# V1_8.net
KiCad netlist of a schematic drawn in Altium Designer
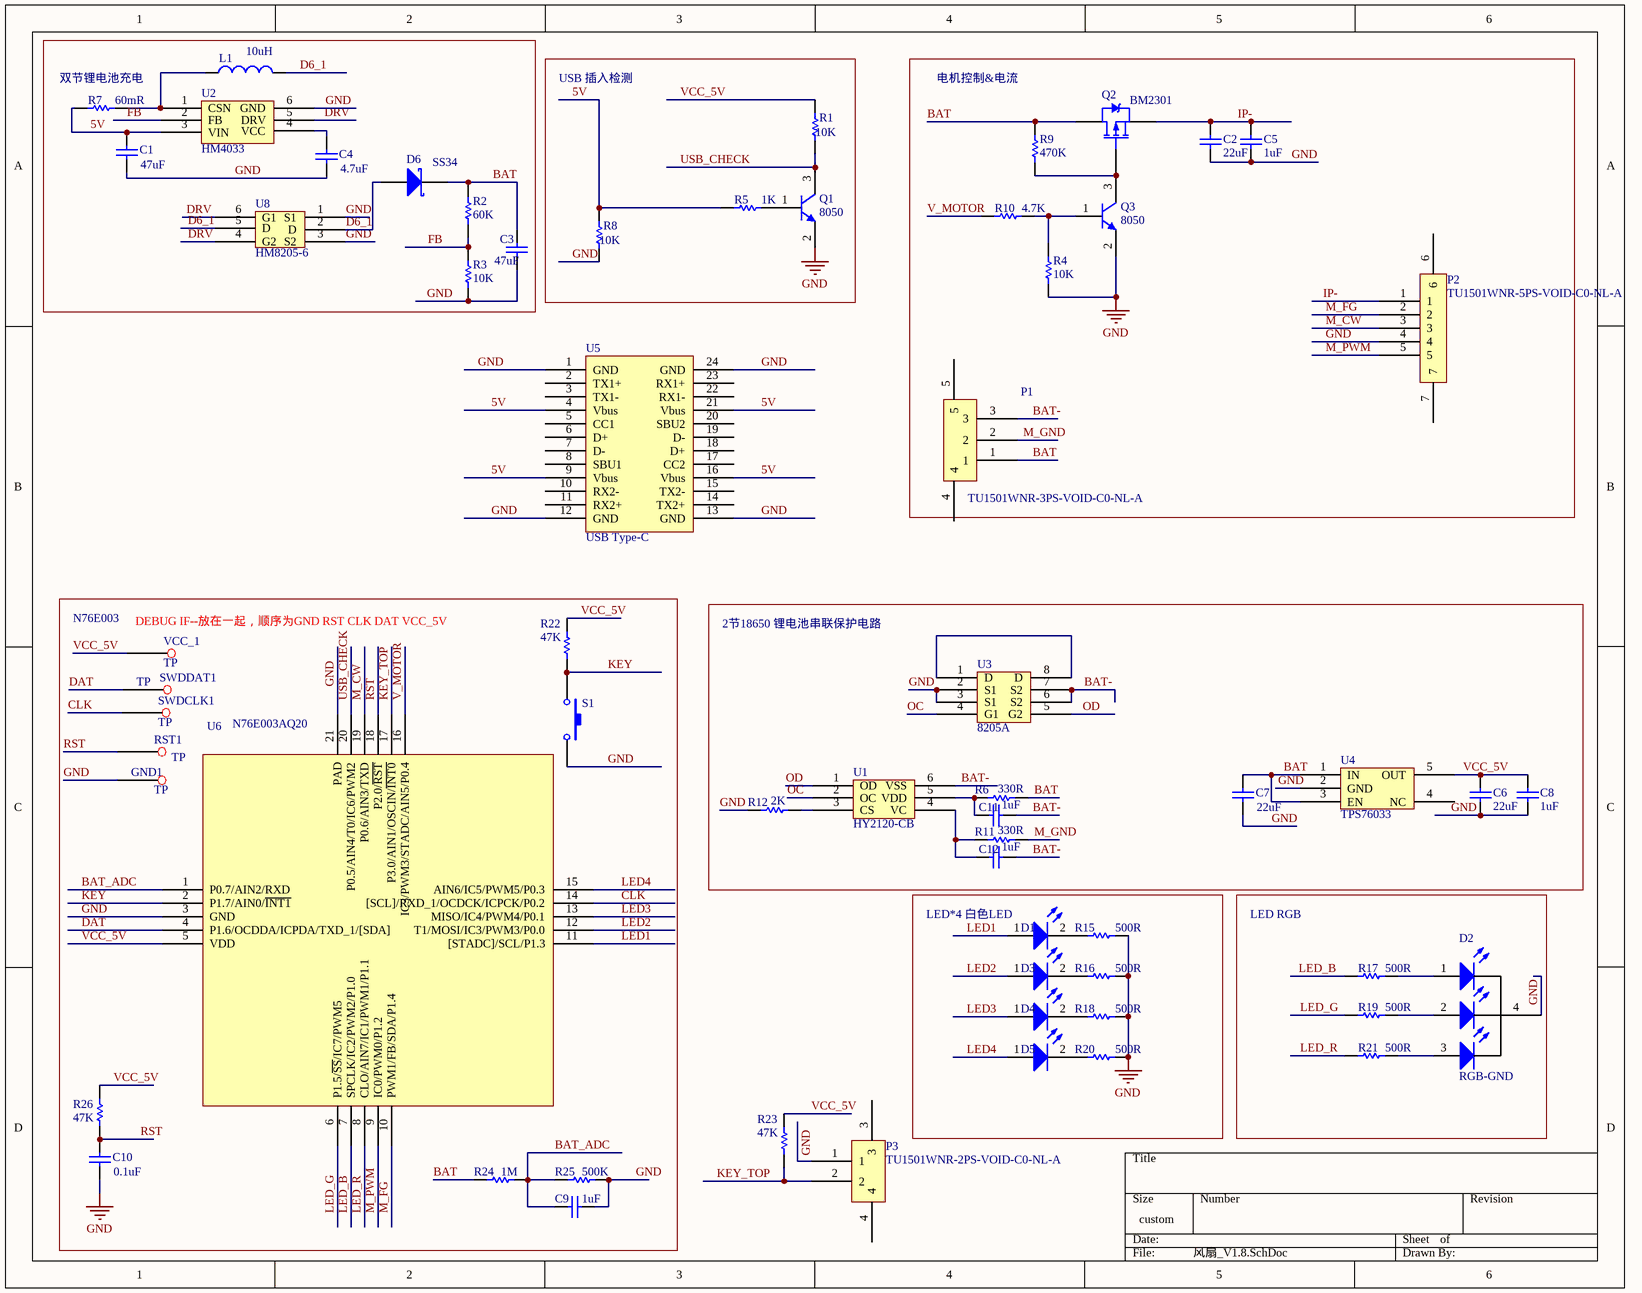
[diagram p0: 风扇_V1.8.SchDoc]

(export (version "E")
  (design (tool "Eeschema 10.0.6"))
  (components
    (comp (ref "C1")
      (value "47uF")
      (footprint "C-0603")
      (description "Capacitor")
      (fields (field (name "PUBLISHER") "Altium Limited"))
      (libsource (lib "Miscellaneous Devices") (part "Cap"))
    )
    (comp (ref "C2")
      (value "22uF")
      (footprint "C-0603")
      (description "Capacitor")
      (fields (field (name "PUBLISHER") "Altium Limited"))
      (libsource (lib "Miscellaneous Devices") (part "Cap"))
    )
    (comp (ref "C3")
      (value "47uF")
      (footprint "C-0603")
      (description "Capacitor")
      (fields (field (name "PUBLISHER") "Altium Limited"))
      (libsource (lib "Miscellaneous Devices") (part "Cap"))
    )
    (comp (ref "C4")
      (value "4.7uF")
      (footprint "C-0402")
      (description "Capacitor")
      (fields (field (name "PUBLISHER") "Altium Limited"))
      (libsource (lib "Miscellaneous Devices") (part "Cap"))
    )
    (comp (ref "C5")
      (value "1uF")
      (footprint "C-0402")
      (description "Capacitor")
      (fields (field (name "PUBLISHER") "Altium Limited"))
      (libsource (lib "Miscellaneous Devices") (part "Cap"))
    )
    (comp (ref "C6")
      (value "22uF")
      (footprint "C-0603")
      (description "Capacitor")
      (fields (field (name "PUBLISHER") "Altium Limited"))
      (libsource (lib "Miscellaneous Devices") (part "Cap"))
    )
    (comp (ref "C7")
      (value "22uF")
      (footprint "C-0603")
      (description "Capacitor")
      (fields (field (name "PUBLISHER") "Altium Limited"))
      (libsource (lib "Miscellaneous Devices") (part "Cap"))
    )
    (comp (ref "C8")
      (value "1uF")
      (footprint "C-0402")
      (description "Capacitor")
      (fields (field (name "PUBLISHER") "Altium Limited"))
      (libsource (lib "Miscellaneous Devices") (part "Cap"))
    )
    (comp (ref "C9")
      (value "1uF")
      (footprint "C-0402")
      (description "Capacitor")
      (fields (field (name "PUBLISHER") "Altium Limited"))
      (libsource (lib "Miscellaneous Devices") (part "Cap"))
    )
    (comp (ref "C10")
      (value "0.1uF")
      (footprint "C-0402")
      (description "Capacitor")
      (fields (field (name "PUBLISHER") "Altium Limited"))
      (libsource (lib "Miscellaneous Devices") (part "Cap"))
    )
    (comp (ref "C11")
      (value "1uF")
      (footprint "C-0402")
      (description "Capacitor")
      (fields (field (name "PUBLISHER") "Altium Limited"))
      (libsource (lib "Miscellaneous Devices") (part "Cap"))
    )
    (comp (ref "C12")
      (value "1uF")
      (footprint "C-0402")
      (description "Capacitor")
      (fields (field (name "PUBLISHER") "Altium Limited"))
      (libsource (lib "Miscellaneous Devices") (part "Cap"))
    )
    (comp (ref "D1")
      (value "LED0")
      (footprint "LED-0603")
      (description "Typical INFRARED GaAs LED")
      (fields (field (name "PUBLISHER") "Altium Limited"))
      (libsource (lib "Miscellaneous Devices") (part "LED0"))
    )
    (comp (ref "D2")
      (value "RGB-GND")
      (footprint "0603*2-LED")
      (libsource (lib "Others_IC_SCH_LIB") (part "RGB-GND"))
    )
    (comp (ref "D3")
      (value "LED0")
      (footprint "LED-0603")
      (description "Typical INFRARED GaAs LED")
      (fields (field (name "PUBLISHER") "Altium Limited"))
      (libsource (lib "Miscellaneous Devices") (part "LED0"))
    )
    (comp (ref "D4")
      (value "LED0")
      (footprint "LED-0603")
      (description "Typical INFRARED GaAs LED")
      (fields (field (name "PUBLISHER") "Altium Limited"))
      (libsource (lib "Miscellaneous Devices") (part "LED0"))
    )
    (comp (ref "D5")
      (value "LED0")
      (footprint "LED-0603")
      (description "Typical INFRARED GaAs LED")
      (fields (field (name "PUBLISHER") "Altium Limited"))
      (libsource (lib "Miscellaneous Devices") (part "LED0"))
    )
    (comp (ref "D6")
      (value "SS34")
      (footprint "HM4033 V1.0:DSMD")
      (description "Schottky Rectifier")
      (fields (field (name "PUBLISHER") "Altium Limited"))
      (libsource (lib "Miscellaneous Devices") (part "Diode 10TQ035"))
    )
    (comp (ref "GND1") (value "TP") (footprint "TP-1.5") (libsource (lib "Others_IC_SCH_LIB") (part "TP")))
    (comp (ref "L1")
      (value "10uH")
      (footprint "L-SMD")
      (description "Inductor")
      (fields (field (name "PUBLISHER") "Altium Limited"))
      (libsource (lib "Miscellaneous Devices") (part "Inductor"))
    )
    (comp (ref "P1")
      (value "TU1501WNR-3PS-VOID-C0-NL-A")
      (footprint "TU1501WNR-3PS-VOID-*-NL-A")
      (libsource (lib "Others_IC_SCH_LIB") (part "TU1501WNR-3PS-VOID-C0-NL-A"))
    )
    (comp (ref "P2")
      (value "TU1501WNR-5PS-VOID-C0-NL-A")
      (footprint "TU1501WNR-5PS-VOID-*-NL-A")
      (libsource (lib "Others_IC_SCH_LIB") (part "TU1501WNR-5PS-VOID-C0-NL-A"))
    )
    (comp (ref "P3")
      (value "TU1501WNR-2PS-VOID-C0-NL-A")
      (footprint "TU1501WNR-2PS-VOID-*-NL-A")
      (libsource (lib "Others_IC_SCH_LIB") (part "TU1501WNR-2PS-VOID-C0-NL-A"))
    )
    (comp (ref "Q1")
      (value "8050")
      (footprint "SOT-23")
      (description "NPN Bipolar Transistor")
      (fields (field (name "PUBLISHER") "Altium Limited"))
      (libsource (lib "Miscellaneous Devices") (part "NPN"))
    )
    (comp (ref "Q2")
      (value "BM2301")
      (footprint "SOT-23")
      (description "P-Channel Power MOSFET")
      (fields (field (name "PUBLISHER") "Altium Limited"))
      (libsource (lib "Miscellaneous Devices") (part "PMOS-2"))
    )
    (comp (ref "Q3")
      (value "8050")
      (footprint "SOT-23")
      (description "NPN Bipolar Transistor")
      (fields (field (name "PUBLISHER") "Altium Limited"))
      (libsource (lib "Miscellaneous Devices") (part "NPN"))
    )
    (comp (ref "R1")
      (value "10K")
      (footprint "R-0402")
      (description "Resistor")
      (fields (field (name "PUBLISHER") "Altium Limited"))
      (libsource (lib "Miscellaneous Devices") (part "Res1"))
    )
    (comp (ref "R2")
      (value "60K")
      (footprint "R-0402")
      (description "Resistor")
      (fields (field (name "PUBLISHER") "Altium Limited"))
      (libsource (lib "Miscellaneous Devices") (part "Res1"))
    )
    (comp (ref "R3")
      (value "10K")
      (footprint "R-0402")
      (description "Resistor")
      (fields (field (name "PUBLISHER") "Altium Limited"))
      (libsource (lib "Miscellaneous Devices") (part "Res1"))
    )
    (comp (ref "R4")
      (value "10K")
      (footprint "R-0402")
      (description "Resistor")
      (fields (field (name "PUBLISHER") "Altium Limited"))
      (libsource (lib "Miscellaneous Devices") (part "Res1"))
    )
    (comp (ref "R5")
      (value "1K")
      (footprint "R-0402")
      (description "Resistor")
      (fields (field (name "PUBLISHER") "Altium Limited"))
      (libsource (lib "Miscellaneous Devices") (part "Res1"))
    )
    (comp (ref "R6")
      (value "330R")
      (footprint "R-0402")
      (description "Resistor")
      (fields (field (name "PUBLISHER") "Altium Limited"))
      (libsource (lib "Miscellaneous Devices") (part "Res1"))
    )
    (comp (ref "R7")
      (value "60mR")
      (footprint "R-0402")
      (description "Resistor")
      (fields (field (name "PUBLISHER") "Altium Limited"))
      (libsource (lib "Miscellaneous Devices") (part "Res1"))
    )
    (comp (ref "R8")
      (value "10K")
      (footprint "R-0402")
      (description "Resistor")
      (fields (field (name "PUBLISHER") "Altium Limited"))
      (libsource (lib "Miscellaneous Devices") (part "Res1"))
    )
    (comp (ref "R9")
      (value "470K")
      (footprint "R-0402")
      (description "Resistor")
      (fields (field (name "PUBLISHER") "Altium Limited"))
      (libsource (lib "Miscellaneous Devices") (part "Res1"))
    )
    (comp (ref "R10")
      (value "4.7K")
      (footprint "R-0402")
      (description "Resistor")
      (fields (field (name "PUBLISHER") "Altium Limited"))
      (libsource (lib "Miscellaneous Devices") (part "Res1"))
    )
    (comp (ref "R11")
      (value "330R")
      (footprint "R-0402")
      (description "Resistor")
      (fields (field (name "PUBLISHER") "Altium Limited"))
      (libsource (lib "Miscellaneous Devices") (part "Res1"))
    )
    (comp (ref "R12")
      (value "2K")
      (footprint "R-0402")
      (description "Resistor")
      (fields (field (name "PUBLISHER") "Altium Limited"))
      (libsource (lib "Miscellaneous Devices") (part "Res1"))
    )
    (comp (ref "R15")
      (value "500R")
      (footprint "R-0402")
      (description "Resistor")
      (fields (field (name "PUBLISHER") "Altium Limited"))
      (libsource (lib "Miscellaneous Devices") (part "Res1"))
    )
    (comp (ref "R16")
      (value "500R")
      (footprint "R-0402")
      (description "Resistor")
      (fields (field (name "PUBLISHER") "Altium Limited"))
      (libsource (lib "Miscellaneous Devices") (part "Res1"))
    )
    (comp (ref "R17")
      (value "500R")
      (footprint "R-0402")
      (description "Resistor")
      (fields (field (name "PUBLISHER") "Altium Limited"))
      (libsource (lib "Miscellaneous Devices") (part "Res1"))
    )
    (comp (ref "R18")
      (value "500R")
      (footprint "R-0402")
      (description "Resistor")
      (fields (field (name "PUBLISHER") "Altium Limited"))
      (libsource (lib "Miscellaneous Devices") (part "Res1"))
    )
    (comp (ref "R19")
      (value "500R")
      (footprint "R-0402")
      (description "Resistor")
      (fields (field (name "PUBLISHER") "Altium Limited"))
      (libsource (lib "Miscellaneous Devices") (part "Res1"))
    )
    (comp (ref "R20")
      (value "500R")
      (footprint "R-0402")
      (description "Resistor")
      (fields (field (name "PUBLISHER") "Altium Limited"))
      (libsource (lib "Miscellaneous Devices") (part "Res1"))
    )
    (comp (ref "R21")
      (value "500R")
      (footprint "R-0402")
      (description "Resistor")
      (fields (field (name "PUBLISHER") "Altium Limited"))
      (libsource (lib "Miscellaneous Devices") (part "Res1"))
    )
    (comp (ref "R22")
      (value "47K")
      (footprint "R-0402")
      (description "Resistor")
      (fields (field (name "PUBLISHER") "Altium Limited"))
      (libsource (lib "Miscellaneous Devices") (part "Res1"))
    )
    (comp (ref "R23")
      (value "47K")
      (footprint "R-0402")
      (description "Resistor")
      (fields (field (name "PUBLISHER") "Altium Limited"))
      (libsource (lib "Miscellaneous Devices") (part "Res1"))
    )
    (comp (ref "R24")
      (value "1M")
      (footprint "R-0402")
      (description "Resistor")
      (fields (field (name "PUBLISHER") "Altium Limited"))
      (libsource (lib "Miscellaneous Devices") (part "Res1"))
    )
    (comp (ref "R25")
      (value "500K")
      (footprint "R-0402")
      (description "Resistor")
      (fields (field (name "PUBLISHER") "Altium Limited"))
      (libsource (lib "Miscellaneous Devices") (part "Res1"))
    )
    (comp (ref "R26")
      (value "47K")
      (footprint "R-0402")
      (description "Resistor")
      (fields (field (name "PUBLISHER") "Altium Limited"))
      (libsource (lib "Miscellaneous Devices") (part "Res1"))
    )
    (comp (ref "RST1") (value "TP") (footprint "TP-1.5") (libsource (lib "Others_IC_SCH_LIB") (part "TP")))
    (comp (ref "S1")
      (value "SW-PB")
      (footprint "SWITCH-4P-SMT")
      (description "Switch")
      (fields (field (name "PUBLISHER") "Altium Limited"))
      (libsource (lib "Miscellaneous Devices") (part "SW-PB"))
    )
    (comp (ref "SWDCLK1") (value "TP") (footprint "TP-1.5") (libsource (lib "Others_IC_SCH_LIB") (part "TP")))
    (comp (ref "SWDDAT1") (value "TP") (footprint "TP-1.5") (libsource (lib "Others_IC_SCH_LIB") (part "TP")))
    (comp (ref "U1")
      (value "HY2120-CB")
      (footprint "SOT-23-6L")
      (libsource (lib "Others_IC_SCH_LIB") (part "HY2120"))
    )
    (comp (ref "U2")
      (value "HM4033")
      (footprint "SOT-23-6L")
      (libsource (lib "Others_IC_SCH_LIB") (part "HM4033"))
    )
    (comp (ref "U3")
      (value "8205A")
      (footprint "TSSOP8")
      (libsource (lib "Others_IC_SCH_LIB") (part "8205A"))
    )
    (comp (ref "U4")
      (value "TPS76033")
      (footprint "SOT-23-5")
      (libsource (lib "Others_IC_SCH_LIB") (part "TPS76033"))
    )
    (comp (ref "U5")
      (value "USB Type-C")
      (footprint "USB-type C")
      (libsource (lib "Others_IC_SCH_LIB") (part "USB Type-C"))
    )
    (comp (ref "U6")
      (value "N76E003AQ20")
      (footprint "QFN-20 0.4mm")
      (libsource (lib "Others_IC_SCH_LIB") (part "N76E003AQ20"))
    )
    (comp (ref "U8")
      (value "HM8205-6")
      (footprint "SOT-23-6L")
      (libsource (lib "Others_IC_SCH_LIB") (part "HM8205-6"))
    )
    (comp (ref "VCC_1") (value "TP") (footprint "TP-1.5") (libsource (lib "Others_IC_SCH_LIB") (part "TP")))
  )
  (nets
    (net (code "1") (name "/5V") (class "Default")
      (node (ref "C1") (pin "1") (pinfunction "1_1") (pintype "passive"))
      (node (ref "R5") (pin "1") (pinfunction "1_1") (pintype "passive"))
      (node (ref "R7") (pin "2") (pinfunction "2_2") (pintype "passive"))
      (node (ref "R8") (pin "1") (pinfunction "1_1") (pintype "passive"))
      (node (ref "U2") (pin "3") (pinfunction "VIN_3") (pintype "passive"))
      (node (ref "U5") (pin "16") (pinfunction "Vbus_16") (pintype "passive"))
      (node (ref "U5") (pin "21") (pinfunction "Vbus_21") (pintype "passive"))
      (node (ref "U5") (pin "4") (pinfunction "Vbus_4") (pintype "passive"))
      (node (ref "U5") (pin "9") (pinfunction "Vbus_9") (pintype "passive"))
    )
    (net (code "2") (name "/BAT") (class "Default")
      (node (ref "C3") (pin "2") (pinfunction "2_2") (pintype "passive"))
      (node (ref "C7") (pin "2") (pinfunction "2_2") (pintype "passive"))
      (node (ref "D6") (pin "1") (pinfunction "K_1") (pintype "passive"))
      (node (ref "P1") (pin "1") (pinfunction "1_1") (pintype "passive"))
      (node (ref "Q2") (pin "2") (pinfunction "D_2") (pintype "passive"))
      (node (ref "R2") (pin "1") (pinfunction "1_1") (pintype "passive"))
      (node (ref "R24") (pin "1") (pinfunction "1_1") (pintype "passive"))
      (node (ref "R6") (pin "2") (pinfunction "2_2") (pintype "passive"))
      (node (ref "R9") (pin "2") (pinfunction "2_2") (pintype "passive"))
      (node (ref "U4") (pin "1") (pinfunction "IN_1") (pintype "passive"))
      (node (ref "U4") (pin "3") (pinfunction "EN_3") (pintype "passive"))
    )
    (net (code "3") (name "/BAT-") (class "Default")
      (node (ref "C11") (pin "1") (pinfunction "1_1") (pintype "passive"))
      (node (ref "C12") (pin "1") (pinfunction "1_1") (pintype "passive"))
      (node (ref "P1") (pin "3") (pinfunction "3_3") (pintype "passive"))
      (node (ref "U1") (pin "6") (pinfunction "VSS_6") (pintype "passive"))
      (node (ref "U3") (pin "6") (pinfunction "S2_6") (pintype "passive"))
      (node (ref "U3") (pin "7") (pinfunction "S2_7") (pintype "passive"))
    )
    (net (code "4") (name "/BAT_ADC") (class "Default")
      (node (ref "C9") (pin "2") (pinfunction "2_2") (pintype "passive"))
      (node (ref "R24") (pin "2") (pinfunction "2_2") (pintype "passive"))
      (node (ref "R25") (pin "1") (pinfunction "1_1") (pintype "passive"))
      (node (ref "U6") (pin "1") (pinfunction "P0.7/AIN2/RXD_1") (pintype "passive"))
    )
    (net (code "5") (name "/CLK") (class "Default")
      (node (ref "SWDCLK1") (pin "1") (pinfunction "1_1") (pintype "passive"))
      (node (ref "U6") (pin "14") (pinfunction "[SCL]/RXD_1/OCDCK/ICPCK/P0.2_14") (pintype "passive"))
    )
    (net (code "6") (name "/D6_1") (class "Default")
      (node (ref "D6") (pin "3") (pinfunction "A_3") (pintype "passive"))
      (node (ref "L1") (pin "2") (pinfunction "2_2") (pintype "passive"))
      (node (ref "U8") (pin "2") (pinfunction "D_2") (pintype "passive"))
      (node (ref "U8") (pin "5") (pinfunction "D_5") (pintype "passive"))
    )
    (net (code "7") (name "/DAT") (class "Default")
      (node (ref "SWDDAT1") (pin "1") (pinfunction "1_1") (pintype "passive"))
      (node (ref "U6") (pin "4") (pinfunction "P1.6/OCDDA/ICPDA/TXD_1/[SDA]_4") (pintype "passive"))
    )
    (net (code "8") (name "/DRV") (class "Default")
      (node (ref "U2") (pin "5") (pinfunction "DRV_5") (pintype "passive"))
      (node (ref "U8") (pin "4") (pinfunction "G2_4") (pintype "passive"))
      (node (ref "U8") (pin "6") (pinfunction "G1_6") (pintype "passive"))
    )
    (net (code "9") (name "/FB") (class "Default")
      (node (ref "R2") (pin "2") (pinfunction "2_2") (pintype "passive"))
      (node (ref "R3") (pin "1") (pinfunction "1_1") (pintype "passive"))
      (node (ref "U2") (pin "2") (pinfunction "FB_2") (pintype "passive"))
    )
    (net (code "10") (name "/IP-") (class "Default")
      (node (ref "C2") (pin "2") (pinfunction "2_2") (pintype "passive"))
      (node (ref "C5") (pin "2") (pinfunction "2_2") (pintype "passive"))
      (node (ref "P2") (pin "1") (pinfunction "1_1") (pintype "passive"))
      (node (ref "Q2") (pin "3") (pinfunction "S_3") (pintype "passive"))
    )
    (net (code "11") (name "/KEY") (class "Default")
      (node (ref "R22") (pin "1") (pinfunction "1_1") (pintype "passive"))
      (node (ref "S1") (pin "1") (pinfunction "1_1") (pintype "passive"))
      (node (ref "U6") (pin "2") (pinfunction "P1.7/AIN0/~{INT1}_2") (pintype "passive"))
    )
    (net (code "12") (name "/KEY_TOP") (class "Default")
      (node (ref "P3") (pin "2") (pinfunction "2_2") (pintype "passive"))
      (node (ref "R23") (pin "1") (pinfunction "1_1") (pintype "passive"))
      (node (ref "U6") (pin "17") (pinfunction "P3.0/AIN1/OSCIN/~{INT0}_17") (pintype "passive"))
    )
    (net (code "13") (name "/LED1") (class "Default")
      (node (ref "D1") (pin "1") (pinfunction "A_1") (pintype "passive"))
      (node (ref "U6") (pin "11") (pinfunction "[STADC]/SCL/P1.3_11") (pintype "passive"))
    )
    (net (code "14") (name "/LED2") (class "Default")
      (node (ref "D3") (pin "1") (pinfunction "A_1") (pintype "passive"))
      (node (ref "U6") (pin "12") (pinfunction "T1/MOSI/IC3/PWM3/P0.0_12") (pintype "passive"))
    )
    (net (code "15") (name "/LED3") (class "Default")
      (node (ref "D4") (pin "1") (pinfunction "A_1") (pintype "passive"))
      (node (ref "U6") (pin "13") (pinfunction "MISO/IC4/PWM4/P0.1_13") (pintype "passive"))
    )
    (net (code "16") (name "/LED4") (class "Default")
      (node (ref "D5") (pin "1") (pinfunction "A_1") (pintype "passive"))
      (node (ref "U6") (pin "15") (pinfunction "AIN6/IC5/PWM5/P0.3_15") (pintype "passive"))
    )
    (net (code "17") (name "/LED_B") (class "Default")
      (node (ref "R17") (pin "1") (pinfunction "1_1") (pintype "passive"))
      (node (ref "U6") (pin "7") (pinfunction "SPCLK/IC2/PWM2/P1.0_7") (pintype "passive"))
    )
    (net (code "18") (name "/LED_G") (class "Default")
      (node (ref "R19") (pin "1") (pinfunction "1_1") (pintype "passive"))
      (node (ref "U6") (pin "6") (pinfunction "P1.5/~{SS}/IC7/PWM5_6") (pintype "passive"))
    )
    (net (code "19") (name "/LED_R") (class "Default")
      (node (ref "R21") (pin "1") (pinfunction "1_1") (pintype "passive"))
      (node (ref "U6") (pin "8") (pinfunction "CLO/AIN7/IC1/PWM1/P1.1_8") (pintype "passive"))
    )
    (net (code "20") (name "/M_CW") (class "Default")
      (node (ref "P2") (pin "3") (pinfunction "3_3") (pintype "passive"))
      (node (ref "U6") (pin "19") (pinfunction "P0.6/AIN3/TXD_19") (pintype "passive"))
    )
    (net (code "21") (name "/M_FG") (class "Default")
      (node (ref "P2") (pin "2") (pinfunction "2_2") (pintype "passive"))
      (node (ref "U6") (pin "10") (pinfunction "PWM1/FB/SDA/P1.4_10") (pintype "passive"))
    )
    (net (code "22") (name "/M_GND") (class "Default")
      (node (ref "P1") (pin "2") (pinfunction "2_2") (pintype "passive"))
      (node (ref "R11") (pin "2") (pinfunction "2_2") (pintype "passive"))
    )
    (net (code "23") (name "/M_PWM") (class "Default")
      (node (ref "P2") (pin "5") (pinfunction "5_5") (pintype "passive"))
      (node (ref "U6") (pin "9") (pinfunction "IC0/PWM0/P1.2_9") (pintype "passive"))
    )
    (net (code "24") (name "/OC") (class "Default")
      (node (ref "U1") (pin "2") (pinfunction "OC_2") (pintype "passive"))
      (node (ref "U3") (pin "4") (pinfunction "G1_4") (pintype "passive"))
    )
    (net (code "25") (name "/OD") (class "Default")
      (node (ref "U1") (pin "1") (pinfunction "OD_1") (pintype "passive"))
      (node (ref "U3") (pin "5") (pinfunction "G2_5") (pintype "passive"))
    )
    (net (code "26") (name "/RST") (class "Default")
      (node (ref "C10") (pin "2") (pinfunction "2_2") (pintype "passive"))
      (node (ref "R26") (pin "1") (pinfunction "1_1") (pintype "passive"))
      (node (ref "RST1") (pin "1") (pinfunction "1_1") (pintype "passive"))
      (node (ref "U6") (pin "18") (pinfunction "P2.0/~{RST}_18") (pintype "passive"))
    )
    (net (code "27") (name "/USB_CHECK") (class "Default")
      (node (ref "Q1") (pin "3") (pinfunction "C_3") (pintype "passive"))
      (node (ref "R1") (pin "1") (pinfunction "1_1") (pintype "passive"))
      (node (ref "U6") (pin "20") (pinfunction "P0.5/AIN4/T0/IC6/PWM2_20") (pintype "passive"))
    )
    (net (code "28") (name "/VCC_5V") (class "Default")
      (node (ref "C6") (pin "2") (pinfunction "2_2") (pintype "passive"))
      (node (ref "C8") (pin "2") (pinfunction "2_2") (pintype "passive"))
      (node (ref "R1") (pin "2") (pinfunction "2_2") (pintype "passive"))
      (node (ref "R22") (pin "2") (pinfunction "2_2") (pintype "passive"))
      (node (ref "R23") (pin "2") (pinfunction "2_2") (pintype "passive"))
      (node (ref "R26") (pin "2") (pinfunction "2_2") (pintype "passive"))
      (node (ref "U4") (pin "5") (pinfunction "OUT_5") (pintype "passive"))
      (node (ref "U6") (pin "5") (pinfunction "VDD_5") (pintype "passive"))
      (node (ref "VCC_1") (pin "1") (pinfunction "1_1") (pintype "passive"))
    )
    (net (code "29") (name "/V_MOTOR") (class "Default")
      (node (ref "R10") (pin "1") (pinfunction "1_1") (pintype "passive"))
      (node (ref "U6") (pin "16") (pinfunction "IC3/PWM3/STADC/AIN5/P0.4_16") (pintype "passive"))
    )
    (net (code "30") (name "GND") (class "Default")
      (node (ref "C1") (pin "2") (pinfunction "2_2") (pintype "passive"))
      (node (ref "C10") (pin "1") (pinfunction "1_1") (pintype "passive"))
      (node (ref "C2") (pin "1") (pinfunction "1_1") (pintype "passive"))
      (node (ref "C3") (pin "1") (pinfunction "1_1") (pintype "passive"))
      (node (ref "C4") (pin "2") (pinfunction "2_2") (pintype "passive"))
      (node (ref "C5") (pin "1") (pinfunction "1_1") (pintype "passive"))
      (node (ref "C6") (pin "1") (pinfunction "1_1") (pintype "passive"))
      (node (ref "C7") (pin "1") (pinfunction "1_1") (pintype "passive"))
      (node (ref "C8") (pin "1") (pinfunction "1_1") (pintype "passive"))
      (node (ref "C9") (pin "1") (pinfunction "1_1") (pintype "passive"))
      (node (ref "D2") (pin "4") (pinfunction "4_4") (pintype "passive"))
      (node (ref "GND1") (pin "1") (pinfunction "1_1") (pintype "passive"))
      (node (ref "P2") (pin "4") (pinfunction "4_4") (pintype "passive"))
      (node (ref "P3") (pin "1") (pinfunction "1_1") (pintype "passive"))
      (node (ref "Q1") (pin "2") (pinfunction "E_2") (pintype "passive"))
      (node (ref "Q3") (pin "2") (pinfunction "E_2") (pintype "passive"))
      (node (ref "R12") (pin "1") (pinfunction "1_1") (pintype "passive"))
      (node (ref "R15") (pin "2") (pinfunction "2_2") (pintype "passive"))
      (node (ref "R16") (pin "2") (pinfunction "2_2") (pintype "passive"))
      (node (ref "R18") (pin "2") (pinfunction "2_2") (pintype "passive"))
      (node (ref "R20") (pin "2") (pinfunction "2_2") (pintype "passive"))
      (node (ref "R25") (pin "2") (pinfunction "2_2") (pintype "passive"))
      (node (ref "R3") (pin "2") (pinfunction "2_2") (pintype "passive"))
      (node (ref "R4") (pin "1") (pinfunction "1_1") (pintype "passive"))
      (node (ref "R8") (pin "2") (pinfunction "2_2") (pintype "passive"))
      (node (ref "S1") (pin "2") (pinfunction "2_2") (pintype "passive"))
      (node (ref "U2") (pin "6") (pinfunction "GND_6") (pintype "passive"))
      (node (ref "U3") (pin "2") (pinfunction "S1_2") (pintype "passive"))
      (node (ref "U3") (pin "3") (pinfunction "S1_3") (pintype "passive"))
      (node (ref "U4") (pin "2") (pinfunction "GND_2") (pintype "passive"))
      (node (ref "U5") (pin "1") (pinfunction "GND_1") (pintype "passive"))
      (node (ref "U5") (pin "12") (pinfunction "GND_12") (pintype "passive"))
      (node (ref "U5") (pin "13") (pinfunction "GND_13") (pintype "passive"))
      (node (ref "U5") (pin "24") (pinfunction "GND_24") (pintype "passive"))
      (node (ref "U6") (pin "21") (pinfunction "PAD_21") (pintype "passive"))
      (node (ref "U6") (pin "3") (pinfunction "GND_3") (pintype "passive"))
      (node (ref "U8") (pin "1") (pinfunction "S1_1") (pintype "passive"))
      (node (ref "U8") (pin "3") (pinfunction "S2_3") (pintype "passive"))
    )
    (net (code "31") (name "Net-(D1-K)") (class "Default")
      (node (ref "D1") (pin "2") (pinfunction "K_2") (pintype "passive"))
      (node (ref "R15") (pin "1") (pinfunction "1_1") (pintype "passive"))
    )
    (net (code "32") (name "Net-(D2-Pad1)") (class "Default")
      (node (ref "D2") (pin "1") (pinfunction "1_1") (pintype "passive"))
      (node (ref "R17") (pin "2") (pinfunction "2_2") (pintype "passive"))
    )
    (net (code "33") (name "Net-(D2-Pad2)") (class "Default")
      (node (ref "D2") (pin "2") (pinfunction "2_2") (pintype "passive"))
      (node (ref "R19") (pin "2") (pinfunction "2_2") (pintype "passive"))
    )
    (net (code "34") (name "Net-(D2-Pad3)") (class "Default")
      (node (ref "D2") (pin "3") (pinfunction "3_3") (pintype "passive"))
      (node (ref "R21") (pin "2") (pinfunction "2_2") (pintype "passive"))
    )
    (net (code "35") (name "Net-(D3-K)") (class "Default")
      (node (ref "D3") (pin "2") (pinfunction "K_2") (pintype "passive"))
      (node (ref "R16") (pin "1") (pinfunction "1_1") (pintype "passive"))
    )
    (net (code "36") (name "Net-(D4-K)") (class "Default")
      (node (ref "D4") (pin "2") (pinfunction "K_2") (pintype "passive"))
      (node (ref "R18") (pin "1") (pinfunction "1_1") (pintype "passive"))
    )
    (net (code "37") (name "Net-(D5-K)") (class "Default")
      (node (ref "D5") (pin "2") (pinfunction "K_2") (pintype "passive"))
      (node (ref "R20") (pin "1") (pinfunction "1_1") (pintype "passive"))
    )
    (net (code "38") (name "Net-(Q1-B)") (class "Default")
      (node (ref "Q1") (pin "1") (pinfunction "B_1") (pintype "passive"))
      (node (ref "R5") (pin "2") (pinfunction "2_2") (pintype "passive"))
    )
    (net (code "39") (name "Net-(Q2-G)") (class "Default")
      (node (ref "Q2") (pin "1") (pinfunction "G_1") (pintype "passive"))
      (node (ref "Q3") (pin "3") (pinfunction "C_3") (pintype "passive"))
      (node (ref "R9") (pin "1") (pinfunction "1_1") (pintype "passive"))
    )
    (net (code "40") (name "Net-(Q3-B)") (class "Default")
      (node (ref "Q3") (pin "1") (pinfunction "B_1") (pintype "passive"))
      (node (ref "R10") (pin "2") (pinfunction "2_2") (pintype "passive"))
      (node (ref "R4") (pin "2") (pinfunction "2_2") (pintype "passive"))
    )
    (net (code "41") (name "Net-(U1-CS)") (class "Default")
      (node (ref "R12") (pin "2") (pinfunction "2_2") (pintype "passive"))
      (node (ref "U1") (pin "3") (pinfunction "CS_3") (pintype "passive"))
    )
    (net (code "42") (name "Net-(U1-VC)") (class "Default")
      (node (ref "C12") (pin "2") (pinfunction "2_2") (pintype "passive"))
      (node (ref "R11") (pin "1") (pinfunction "1_1") (pintype "passive"))
      (node (ref "U1") (pin "4") (pinfunction "VC_4") (pintype "passive"))
    )
    (net (code "43") (name "Net-(U1-VDD)") (class "Default")
      (node (ref "C11") (pin "2") (pinfunction "2_2") (pintype "passive"))
      (node (ref "R6") (pin "1") (pinfunction "1_1") (pintype "passive"))
      (node (ref "U1") (pin "5") (pinfunction "VDD_5") (pintype "passive"))
    )
    (net (code "44") (name "Net-(U2-CSN)") (class "Default")
      (node (ref "L1") (pin "1") (pinfunction "1_1") (pintype "passive"))
      (node (ref "R7") (pin "1") (pinfunction "1_1") (pintype "passive"))
      (node (ref "U2") (pin "1") (pinfunction "CSN_1") (pintype "passive"))
    )
    (net (code "45") (name "Net-(U2-VCC)") (class "Default")
      (node (ref "C4") (pin "1") (pinfunction "1_1") (pintype "passive"))
      (node (ref "U2") (pin "4") (pinfunction "VCC_4") (pintype "passive"))
    )
    (net (code "46") (name "Net-(U3-D-Pad1)") (class "Default")
      (node (ref "U3") (pin "1") (pinfunction "D_1") (pintype "passive"))
      (node (ref "U3") (pin "8") (pinfunction "D_8") (pintype "passive"))
    )
    (net (code "47") (name "unconnected-(P1-Pad4)") (class "Default")
      (node (ref "P1") (pin "4") (pinfunction "4_4") (pintype "passive"))
    )
    (net (code "48") (name "unconnected-(P1-Pad5)") (class "Default")
      (node (ref "P1") (pin "5") (pinfunction "5_5") (pintype "passive"))
    )
    (net (code "49") (name "unconnected-(P2-Pad6)") (class "Default")
      (node (ref "P2") (pin "6") (pinfunction "6_6") (pintype "passive"))
    )
    (net (code "50") (name "unconnected-(P2-Pad7)") (class "Default")
      (node (ref "P2") (pin "7") (pinfunction "7_7") (pintype "passive"))
    )
    (net (code "51") (name "unconnected-(P3-Pad3)") (class "Default")
      (node (ref "P3") (pin "3") (pinfunction "3_3") (pintype "passive"))
    )
    (net (code "52") (name "unconnected-(P3-Pad4)") (class "Default")
      (node (ref "P3") (pin "4") (pinfunction "4_4") (pintype "passive"))
    )
    (net (code "53") (name "unconnected-(U4-NC-Pad4)") (class "Default")
      (node (ref "U4") (pin "4") (pinfunction "NC_4") (pintype "passive"))
    )
    (net (code "54") (name "unconnected-(U5-CC1-Pad5)") (class "Default")
      (node (ref "U5") (pin "5") (pinfunction "CC1_5") (pintype "passive"))
    )
    (net (code "55") (name "unconnected-(U5-CC2-Pad17)") (class "Default")
      (node (ref "U5") (pin "17") (pinfunction "CC2_17") (pintype "passive"))
    )
    (net (code "56") (name "unconnected-(U5-D+-Pad6)") (class "Default")
      (node (ref "U5") (pin "6") (pinfunction "D+_6") (pintype "passive"))
    )
    (net (code "57") (name "unconnected-(U5-D+-Pad18)") (class "Default")
      (node (ref "U5") (pin "18") (pinfunction "D+_18") (pintype "passive"))
    )
    (net (code "58") (name "unconnected-(U5-D--Pad7)") (class "Default")
      (node (ref "U5") (pin "7") (pinfunction "D-_7") (pintype "passive"))
    )
    (net (code "59") (name "unconnected-(U5-D--Pad19)") (class "Default")
      (node (ref "U5") (pin "19") (pinfunction "D-_19") (pintype "passive"))
    )
    (net (code "60") (name "unconnected-(U5-RX1+-Pad23)") (class "Default")
      (node (ref "U5") (pin "23") (pinfunction "RX1+_23") (pintype "passive"))
    )
    (net (code "61") (name "unconnected-(U5-RX1--Pad22)") (class "Default")
      (node (ref "U5") (pin "22") (pinfunction "RX1-_22") (pintype "passive"))
    )
    (net (code "62") (name "unconnected-(U5-RX2+-Pad11)") (class "Default")
      (node (ref "U5") (pin "11") (pinfunction "RX2+_11") (pintype "passive"))
    )
    (net (code "63") (name "unconnected-(U5-RX2--Pad10)") (class "Default")
      (node (ref "U5") (pin "10") (pinfunction "RX2-_10") (pintype "passive"))
    )
    (net (code "64") (name "unconnected-(U5-SBU1-Pad8)") (class "Default")
      (node (ref "U5") (pin "8") (pinfunction "SBU1_8") (pintype "passive"))
    )
    (net (code "65") (name "unconnected-(U5-SBU2-Pad20)") (class "Default")
      (node (ref "U5") (pin "20") (pinfunction "SBU2_20") (pintype "passive"))
    )
    (net (code "66") (name "unconnected-(U5-TX1+-Pad2)") (class "Default")
      (node (ref "U5") (pin "2") (pinfunction "TX1+_2") (pintype "passive"))
    )
    (net (code "67") (name "unconnected-(U5-TX1--Pad3)") (class "Default")
      (node (ref "U5") (pin "3") (pinfunction "TX1-_3") (pintype "passive"))
    )
    (net (code "68") (name "unconnected-(U5-TX2+-Pad14)") (class "Default")
      (node (ref "U5") (pin "14") (pinfunction "TX2+_14") (pintype "passive"))
    )
    (net (code "69") (name "unconnected-(U5-TX2--Pad15)") (class "Default")
      (node (ref "U5") (pin "15") (pinfunction "TX2-_15") (pintype "passive"))
    )
  )
)
